# Connectors.net
KiCad netlist of a schematic drawn in Altium Designer
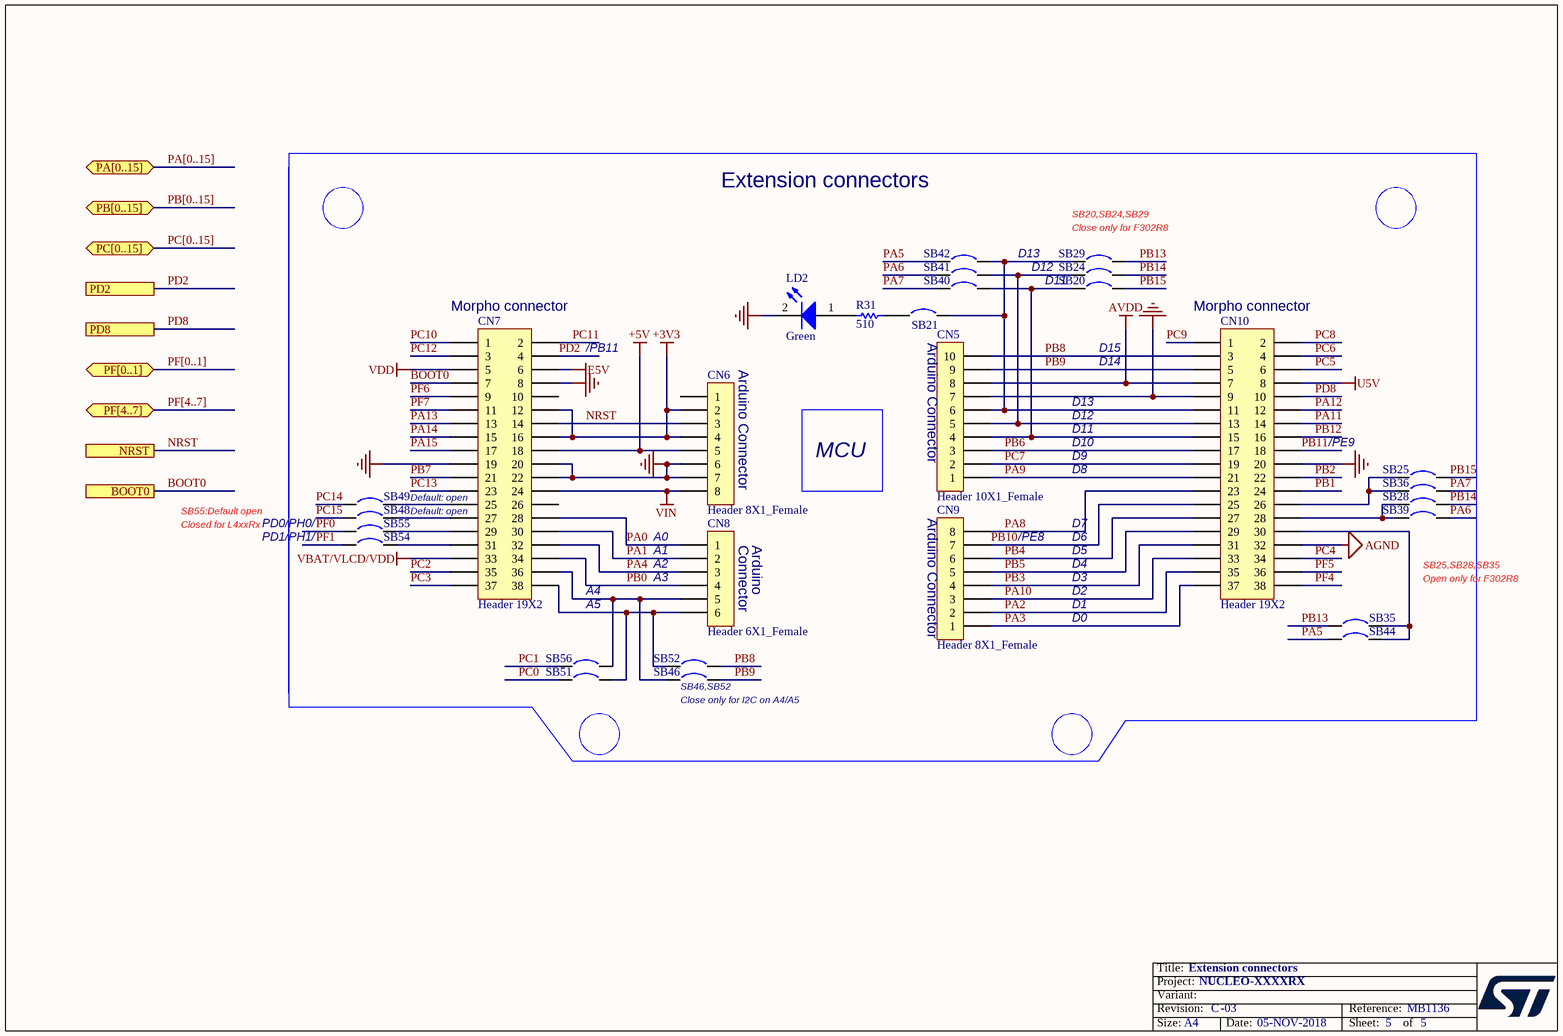
[diagram p0: Connectors.SchDoc]

(export (version "E")
  (design (tool "Eeschema 10.0.6"))
  (components
    (comp (ref "CN5")
      (value "Header 10X1_Female")
      (footprint "1*10P_FEMALE")
      (description "Header, 10-Pin, Single row,female")
      (fields (field (name "PUBLISHER") "Altium Limited"))
      (libsource (lib "Nucleo_64") (part "Header 10X1_Female"))
    )
    (comp (ref "CN6")
      (value "Header 8X1_Female")
      (footprint "1*8P_FEMALE")
      (description "Header, 8-Pin, Single row,female")
      (fields (field (name "PUBLISHER") "Altium Limited"))
      (libsource (lib "Nucleo_64") (part "Header 8X1_Female"))
    )
    (comp (ref "CN7")
      (value "Header 19X2")
      (footprint "2*19P")
      (description "Header, 19-Pin, Dual row")
      (fields (field (name "PUBLISHER") "Altium Limited"))
      (libsource (lib "Nucleo_64_1") (part "Header 19X2"))
    )
    (comp (ref "CN8")
      (value "Header 6X1_Female")
      (footprint "1*6P_FEMALE")
      (description "Header, 6-Pin, Single row,female")
      (fields (field (name "PUBLISHER") "Altium Limited"))
      (libsource (lib "Nucleo_64") (part "Header 6X1_Female"))
    )
    (comp (ref "CN9")
      (value "Header 8X1_Female")
      (footprint "1*8P_FEMALE")
      (description "Header, 8-Pin, Single row,female")
      (fields (field (name "PUBLISHER") "Altium Limited"))
      (libsource (lib "") (part "Header 8X1_Female_1"))
    )
    (comp (ref "CN10")
      (value "Header 19X2")
      (footprint "2*19P")
      (description "Header, 19-Pin, Dual row")
      (fields (field (name "PUBLISHER") "Altium Limited"))
      (libsource (lib "Nucleo_64_1") (part "Header 19X2"))
    )
    (comp (ref "LD2")
      (value "Green")
      (footprint "0603D")
      (description "Typical RED, GREEN, YELLOW, AMBER GaAs LED")
      (fields (field (name "PUBLISHER") "Altium Limited"))
      (libsource (lib "Miscellaneous Devices") (part "LED2"))
    )
    (comp (ref "R31")
      (value "510")
      (footprint "0603R")
      (description "Resistor")
      (fields (field (name "PUBLISHER") "Altium Limited"))
      (libsource (lib "Miscellaneous Devices") (part "Res1"))
    )
    (comp (ref "SB20")
      (value "Circuit Breaker")
      (footprint "JP2_SMD")
      (fields (field (name "PUBLISHER") "Altium Limited"))
      (libsource (lib "MCD_TOOLS") (part "Circuit Breaker"))
    )
    (comp (ref "SB21")
      (value "Circuit Breaker")
      (footprint "JP2_SMD")
      (fields (field (name "PUBLISHER") "Altium Limited"))
      (libsource (lib "MCD_TOOLS") (part "Circuit Breaker"))
    )
    (comp (ref "SB24")
      (value "Circuit Breaker")
      (footprint "JP2_SMD")
      (fields (field (name "PUBLISHER") "Altium Limited"))
      (libsource (lib "MCD_TOOLS") (part "Circuit Breaker"))
    )
    (comp (ref "SB25")
      (value "Circuit Breaker")
      (footprint "JP2_SMD")
      (fields (field (name "PUBLISHER") "Altium Limited"))
      (libsource (lib "") (part "Circuit Breaker_1"))
    )
    (comp (ref "SB28")
      (value "Circuit Breaker")
      (footprint "JP2_SMD")
      (fields (field (name "PUBLISHER") "Altium Limited"))
      (libsource (lib "") (part "Circuit Breaker_1"))
    )
    (comp (ref "SB29")
      (value "Circuit Breaker")
      (footprint "JP2_SMD")
      (fields (field (name "PUBLISHER") "Altium Limited"))
      (libsource (lib "MCD_TOOLS") (part "Circuit Breaker"))
    )
    (comp (ref "SB35")
      (value "Circuit Breaker")
      (footprint "JP2_SMD")
      (fields (field (name "PUBLISHER") "Altium Limited"))
      (libsource (lib "") (part "Circuit Breaker_1"))
    )
    (comp (ref "SB36")
      (value "Circuit Breaker")
      (footprint "JP2_SMD")
      (fields (field (name "PUBLISHER") "Altium Limited"))
      (libsource (lib "") (part "Circuit Breaker_1"))
    )
    (comp (ref "SB39")
      (value "Circuit Breaker")
      (footprint "JP2_SMD")
      (fields (field (name "PUBLISHER") "Altium Limited"))
      (libsource (lib "") (part "Circuit Breaker_1"))
    )
    (comp (ref "SB40")
      (value "Circuit Breaker")
      (footprint "JP2_SMD")
      (fields (field (name "PUBLISHER") "Altium Limited"))
      (libsource (lib "MCD_TOOLS") (part "Circuit Breaker"))
    )
    (comp (ref "SB41")
      (value "Circuit Breaker")
      (footprint "JP2_SMD")
      (fields (field (name "PUBLISHER") "Altium Limited"))
      (libsource (lib "MCD_TOOLS") (part "Circuit Breaker"))
    )
    (comp (ref "SB42")
      (value "Circuit Breaker")
      (footprint "JP2_SMD")
      (fields (field (name "PUBLISHER") "Altium Limited"))
      (libsource (lib "MCD_TOOLS") (part "Circuit Breaker"))
    )
    (comp (ref "SB44")
      (value "Circuit Breaker")
      (footprint "JP2_SMD")
      (fields (field (name "PUBLISHER") "Altium Limited"))
      (libsource (lib "") (part "Circuit Breaker_1"))
    )
    (comp (ref "SB46")
      (value "Circuit Breaker")
      (footprint "JP2_SMD")
      (fields (field (name "PUBLISHER") "Altium Limited"))
      (libsource (lib "MCD_TOOLS") (part "Circuit Breaker"))
    )
    (comp (ref "SB48")
      (value "Circuit Breaker")
      (footprint "JP2_SMD")
      (fields (field (name "PUBLISHER") "Altium Limited"))
      (libsource (lib "") (part "Circuit Breaker_1"))
    )
    (comp (ref "SB49")
      (value "Circuit Breaker")
      (footprint "JP2_SMD")
      (fields (field (name "PUBLISHER") "Altium Limited"))
      (libsource (lib "") (part "Circuit Breaker_1"))
    )
    (comp (ref "SB51")
      (value "Circuit Breaker")
      (footprint "JP2_SMD")
      (fields (field (name "PUBLISHER") "Altium Limited"))
      (libsource (lib "MCD_TOOLS") (part "Circuit Breaker"))
    )
    (comp (ref "SB52")
      (value "Circuit Breaker")
      (footprint "JP2_SMD")
      (fields (field (name "PUBLISHER") "Altium Limited"))
      (libsource (lib "MCD_TOOLS") (part "Circuit Breaker"))
    )
    (comp (ref "SB54")
      (value "Circuit Breaker")
      (footprint "JP2_SMD")
      (fields (field (name "PUBLISHER") "Altium Limited"))
      (libsource (lib "") (part "Circuit Breaker_1"))
    )
    (comp (ref "SB55")
      (value "Circuit Breaker")
      (footprint "JP2_SMD")
      (fields (field (name "PUBLISHER") "Altium Limited"))
      (libsource (lib "") (part "Circuit Breaker_1"))
    )
    (comp (ref "SB56")
      (value "Circuit Breaker")
      (footprint "JP2_SMD")
      (fields (field (name "PUBLISHER") "Altium Limited"))
      (libsource (lib "MCD_TOOLS") (part "Circuit Breaker"))
    )
  )
  (nets
    (net (code "1") (name "+3V3") (class "Default")
      (node (ref "CN6") (pin "2") (pinfunction "2_2") (pintype "passive"))
      (node (ref "CN6") (pin "4") (pinfunction "4_4") (pintype "passive"))
      (node (ref "CN7") (pin "12") (pinfunction "12_12") (pintype "passive"))
      (node (ref "CN7") (pin "16") (pinfunction "16_16") (pintype "passive"))
    )
    (net (code "2") (name "+5V") (class "Default")
      (node (ref "CN6") (pin "5") (pinfunction "5_5") (pintype "passive"))
      (node (ref "CN7") (pin "18") (pinfunction "18_18") (pintype "passive"))
    )
    (net (code "3") (name "/BOOT0") (class "Default")
      (node (ref "CN7") (pin "7") (pinfunction "7_7") (pintype "passive"))
    )
    (net (code "4") (name "/NRST") (class "Default")
      (node (ref "CN6") (pin "3") (pinfunction "3_3") (pintype "passive"))
      (node (ref "CN7") (pin "14") (pinfunction "14_14") (pintype "passive"))
    )
    (net (code "5") (name "/PA0") (class "Default")
      (node (ref "CN7") (pin "28") (pinfunction "28_28") (pintype "passive"))
      (node (ref "CN8") (pin "1") (pinfunction "1_1") (pintype "passive"))
    )
    (net (code "6") (name "/PA1") (class "Default")
      (node (ref "CN7") (pin "30") (pinfunction "30_30") (pintype "passive"))
      (node (ref "CN8") (pin "2") (pinfunction "2_2") (pintype "passive"))
    )
    (net (code "7") (name "/PA2") (class "Default")
      (node (ref "CN10") (pin "35") (pinfunction "35_35") (pintype "passive"))
      (node (ref "CN9") (pin "2") (pinfunction "2_2") (pintype "passive"))
    )
    (net (code "8") (name "/PA3") (class "Default")
      (node (ref "CN10") (pin "37") (pinfunction "37_37") (pintype "passive"))
      (node (ref "CN9") (pin "1") (pinfunction "1_1") (pintype "passive"))
    )
    (net (code "9") (name "/PA4") (class "Default")
      (node (ref "CN7") (pin "32") (pinfunction "32_32") (pintype "passive"))
      (node (ref "CN8") (pin "3") (pinfunction "3_3") (pintype "passive"))
    )
    (net (code "10") (name "/PA5") (class "Default")
      (node (ref "SB42") (pin "1") (pinfunction "1_1") (pintype "passive"))
      (node (ref "SB44") (pin "2") (pinfunction "2_2") (pintype "passive"))
    )
    (net (code "11") (name "/PA6") (class "Default")
      (node (ref "SB39") (pin "1") (pinfunction "1_1") (pintype "passive"))
      (node (ref "SB41") (pin "1") (pinfunction "1_1") (pintype "passive"))
    )
    (net (code "12") (name "/PA7") (class "Default")
      (node (ref "SB36") (pin "1") (pinfunction "1_1") (pintype "passive"))
      (node (ref "SB40") (pin "1") (pinfunction "1_1") (pintype "passive"))
    )
    (net (code "13") (name "/PA8") (class "Default")
      (node (ref "CN10") (pin "23") (pinfunction "23_23") (pintype "passive"))
      (node (ref "CN9") (pin "8") (pinfunction "8_8") (pintype "passive"))
    )
    (net (code "14") (name "/PA9") (class "Default")
      (node (ref "CN10") (pin "21") (pinfunction "21_21") (pintype "passive"))
      (node (ref "CN5") (pin "1") (pinfunction "1_1") (pintype "passive"))
    )
    (net (code "15") (name "/PA10") (class "Default")
      (node (ref "CN10") (pin "33") (pinfunction "33_33") (pintype "passive"))
      (node (ref "CN9") (pin "3") (pinfunction "3_3") (pintype "passive"))
    )
    (net (code "16") (name "/PA11") (class "Default")
      (node (ref "CN10") (pin "14") (pinfunction "14_14") (pintype "passive"))
    )
    (net (code "17") (name "/PA12") (class "Default")
      (node (ref "CN10") (pin "12") (pinfunction "12_12") (pintype "passive"))
    )
    (net (code "18") (name "/PA13") (class "Default")
      (node (ref "CN7") (pin "13") (pinfunction "13_13") (pintype "passive"))
    )
    (net (code "19") (name "/PA14") (class "Default")
      (node (ref "CN7") (pin "15") (pinfunction "15_15") (pintype "passive"))
    )
    (net (code "20") (name "/PA15") (class "Default")
      (node (ref "CN7") (pin "17") (pinfunction "17_17") (pintype "passive"))
    )
    (net (code "22") (name "/PB0") (class "Default")
      (node (ref "CN7") (pin "34") (pinfunction "34_34") (pintype "passive"))
      (node (ref "CN8") (pin "4") (pinfunction "4_4") (pintype "passive"))
    )
    (net (code "23") (name "/PB1") (class "Default")
      (node (ref "CN10") (pin "24") (pinfunction "24_24") (pintype "passive"))
    )
    (net (code "24") (name "/PB2") (class "Default")
      (node (ref "CN10") (pin "22") (pinfunction "22_22") (pintype "passive"))
    )
    (net (code "25") (name "/PB3") (class "Default")
      (node (ref "CN10") (pin "31") (pinfunction "31_31") (pintype "passive"))
      (node (ref "CN9") (pin "4") (pinfunction "4_4") (pintype "passive"))
    )
    (net (code "26") (name "/PB4") (class "Default")
      (node (ref "CN10") (pin "27") (pinfunction "27_27") (pintype "passive"))
      (node (ref "CN9") (pin "6") (pinfunction "6_6") (pintype "passive"))
    )
    (net (code "27") (name "/PB5") (class "Default")
      (node (ref "CN10") (pin "29") (pinfunction "29_29") (pintype "passive"))
      (node (ref "CN9") (pin "5") (pinfunction "5_5") (pintype "passive"))
    )
    (net (code "28") (name "/PB6") (class "Default")
      (node (ref "CN10") (pin "17") (pinfunction "17_17") (pintype "passive"))
      (node (ref "CN5") (pin "3") (pinfunction "3_3") (pintype "passive"))
    )
    (net (code "29") (name "/PB7") (class "Default")
      (node (ref "CN7") (pin "21") (pinfunction "21_21") (pintype "passive"))
    )
    (net (code "30") (name "/PB8") (class "Default")
      (node (ref "CN10") (pin "3") (pinfunction "3_3") (pintype "passive"))
      (node (ref "CN5") (pin "10") (pinfunction "10_10") (pintype "passive"))
      (node (ref "SB52") (pin "2") (pinfunction "2_2") (pintype "passive"))
    )
    (net (code "31") (name "/PB9") (class "Default")
      (node (ref "CN10") (pin "5") (pinfunction "5_5") (pintype "passive"))
      (node (ref "CN5") (pin "9") (pinfunction "9_9") (pintype "passive"))
      (node (ref "SB46") (pin "2") (pinfunction "2_2") (pintype "passive"))
    )
    (net (code "32") (name "/PB10") (class "Default")
      (node (ref "CN10") (pin "25") (pinfunction "25_25") (pintype "passive"))
      (node (ref "CN9") (pin "7") (pinfunction "7_7") (pintype "passive"))
    )
    (net (code "33") (name "/PB11") (class "Default")
      (node (ref "CN10") (pin "18") (pinfunction "18_18") (pintype "passive"))
    )
    (net (code "34") (name "/PB12") (class "Default")
      (node (ref "CN10") (pin "16") (pinfunction "16_16") (pintype "passive"))
    )
    (net (code "35") (name "/PB13") (class "Default")
      (node (ref "SB29") (pin "2") (pinfunction "2_2") (pintype "passive"))
      (node (ref "SB35") (pin "2") (pinfunction "2_2") (pintype "passive"))
    )
    (net (code "36") (name "/PB14") (class "Default")
      (node (ref "SB24") (pin "2") (pinfunction "2_2") (pintype "passive"))
      (node (ref "SB28") (pin "1") (pinfunction "1_1") (pintype "passive"))
    )
    (net (code "37") (name "/PB15") (class "Default")
      (node (ref "SB20") (pin "2") (pinfunction "2_2") (pintype "passive"))
      (node (ref "SB25") (pin "1") (pinfunction "1_1") (pintype "passive"))
    )
    (net (code "39") (name "/PC0") (class "Default")
      (node (ref "SB51") (pin "1") (pinfunction "1_1") (pintype "passive"))
    )
    (net (code "40") (name "/PC1") (class "Default")
      (node (ref "SB56") (pin "1") (pinfunction "1_1") (pintype "passive"))
    )
    (net (code "41") (name "/PC2") (class "Default")
      (node (ref "CN7") (pin "35") (pinfunction "35_35") (pintype "passive"))
    )
    (net (code "42") (name "/PC3") (class "Default")
      (node (ref "CN7") (pin "37") (pinfunction "37_37") (pintype "passive"))
    )
    (net (code "43") (name "/PC4") (class "Default")
      (node (ref "CN10") (pin "34") (pinfunction "34_34") (pintype "passive"))
    )
    (net (code "44") (name "/PC5") (class "Default")
      (node (ref "CN10") (pin "6") (pinfunction "6_6") (pintype "passive"))
    )
    (net (code "45") (name "/PC6") (class "Default")
      (node (ref "CN10") (pin "4") (pinfunction "4_4") (pintype "passive"))
    )
    (net (code "46") (name "/PC7") (class "Default")
      (node (ref "CN10") (pin "19") (pinfunction "19_19") (pintype "passive"))
      (node (ref "CN5") (pin "2") (pinfunction "2_2") (pintype "passive"))
    )
    (net (code "47") (name "/PC8") (class "Default")
      (node (ref "CN10") (pin "2") (pinfunction "2_2") (pintype "passive"))
    )
    (net (code "48") (name "/PC9") (class "Default")
      (node (ref "CN10") (pin "1") (pinfunction "1_1") (pintype "passive"))
    )
    (net (code "49") (name "/PC10") (class "Default")
      (node (ref "CN7") (pin "1") (pinfunction "1_1") (pintype "passive"))
    )
    (net (code "50") (name "/PC11") (class "Default")
      (node (ref "CN7") (pin "2") (pinfunction "2_2") (pintype "passive"))
    )
    (net (code "51") (name "/PC12") (class "Default")
      (node (ref "CN7") (pin "3") (pinfunction "3_3") (pintype "passive"))
    )
    (net (code "52") (name "/PC13") (class "Default")
      (node (ref "CN7") (pin "23") (pinfunction "23_23") (pintype "passive"))
    )
    (net (code "53") (name "/PC14") (class "Default")
      (node (ref "SB49") (pin "2") (pinfunction "2_2") (pintype "passive"))
    )
    (net (code "54") (name "/PC15") (class "Default")
      (node (ref "SB48") (pin "2") (pinfunction "2_2") (pintype "passive"))
    )
    (net (code "56") (name "/PD2") (class "Default")
      (node (ref "CN7") (pin "4") (pinfunction "4_4") (pintype "passive"))
    )
    (net (code "57") (name "/PD8") (class "Default")
      (node (ref "CN10") (pin "10") (pinfunction "10_10") (pintype "passive"))
    )
    (net (code "58") (name "/PF0") (class "Default")
      (node (ref "SB55") (pin "2") (pinfunction "2_2") (pintype "passive"))
    )
    (net (code "59") (name "/PF1") (class "Default")
      (node (ref "SB54") (pin "2") (pinfunction "2_2") (pintype "passive"))
    )
    (net (code "60") (name "/PF4") (class "Default")
      (node (ref "CN10") (pin "38") (pinfunction "38_38") (pintype "passive"))
    )
    (net (code "61") (name "/PF5") (class "Default")
      (node (ref "CN10") (pin "36") (pinfunction "36_36") (pintype "passive"))
    )
    (net (code "62") (name "/PF6") (class "Default")
      (node (ref "CN7") (pin "9") (pinfunction "9_9") (pintype "passive"))
    )
    (net (code "63") (name "/PF7") (class "Default")
      (node (ref "CN7") (pin "11") (pinfunction "11_11") (pintype "passive"))
    )
    (net (code "66") (name "AGND") (class "Default")
      (node (ref "CN10") (pin "32") (pinfunction "32_32") (pintype "passive"))
    )
    (net (code "67") (name "AVDD") (class "Default")
      (node (ref "CN10") (pin "7") (pinfunction "7_7") (pintype "passive"))
      (node (ref "CN5") (pin "8") (pinfunction "8_8") (pintype "passive"))
    )
    (net (code "68") (name "E5V") (class "Default")
      (node (ref "CN7") (pin "6") (pinfunction "6_6") (pintype "passive"))
    )
    (net (code "69") (name "GND") (class "Default")
      (node (ref "CN10") (pin "20") (pinfunction "20_20") (pintype "passive"))
      (node (ref "CN10") (pin "9") (pinfunction "9_9") (pintype "passive"))
      (node (ref "CN5") (pin "7") (pinfunction "7_7") (pintype "passive"))
      (node (ref "CN6") (pin "6") (pinfunction "6_6") (pintype "passive"))
      (node (ref "CN6") (pin "7") (pinfunction "7_7") (pintype "passive"))
      (node (ref "CN7") (pin "19") (pinfunction "19_19") (pintype "passive"))
      (node (ref "CN7") (pin "20") (pinfunction "20_20") (pintype "passive"))
      (node (ref "CN7") (pin "22") (pinfunction "22_22") (pintype "passive"))
      (node (ref "CN7") (pin "8") (pinfunction "8_8") (pintype "passive"))
      (node (ref "LD2") (pin "2") (pinfunction "K_2") (pintype "passive"))
    )
    (net (code "70") (name "Net-(CN7-Pad25)") (class "Default")
      (node (ref "CN7") (pin "25") (pinfunction "25_25") (pintype "passive"))
      (node (ref "SB49") (pin "1") (pinfunction "1_1") (pintype "passive"))
    )
    (net (code "71") (name "Net-(CN7-Pad27)") (class "Default")
      (node (ref "CN7") (pin "27") (pinfunction "27_27") (pintype "passive"))
      (node (ref "SB48") (pin "1") (pinfunction "1_1") (pintype "passive"))
    )
    (net (code "72") (name "Net-(CN7-Pad29)") (class "Default")
      (node (ref "CN7") (pin "29") (pinfunction "29_29") (pintype "passive"))
      (node (ref "SB55") (pin "1") (pinfunction "1_1") (pintype "passive"))
    )
    (net (code "73") (name "Net-(CN7-Pad31)") (class "Default")
      (node (ref "CN7") (pin "31") (pinfunction "31_31") (pintype "passive"))
      (node (ref "SB54") (pin "1") (pinfunction "1_1") (pintype "passive"))
    )
    (net (code "74") (name "Net-(CN7-Pad36)") (class "Default")
      (node (ref "CN7") (pin "36") (pinfunction "36_36") (pintype "passive"))
      (node (ref "CN8") (pin "5") (pinfunction "5_5") (pintype "passive"))
      (node (ref "SB46") (pin "1") (pinfunction "1_1") (pintype "passive"))
      (node (ref "SB56") (pin "2") (pinfunction "2_2") (pintype "passive"))
    )
    (net (code "75") (name "Net-(CN7-Pad38)") (class "Default")
      (node (ref "CN7") (pin "38") (pinfunction "38_38") (pintype "passive"))
      (node (ref "CN8") (pin "6") (pinfunction "6_6") (pintype "passive"))
      (node (ref "SB51") (pin "2") (pinfunction "2_2") (pintype "passive"))
      (node (ref "SB52") (pin "1") (pinfunction "1_1") (pintype "passive"))
    )
    (net (code "76") (name "Net-(CN10-Pad11)") (class "Default")
      (node (ref "CN10") (pin "11") (pinfunction "11_11") (pintype "passive"))
      (node (ref "CN5") (pin "6") (pinfunction "6_6") (pintype "passive"))
      (node (ref "SB21") (pin "2") (pinfunction "2_2") (pintype "passive"))
      (node (ref "SB29") (pin "1") (pinfunction "1_1") (pintype "passive"))
      (node (ref "SB42") (pin "2") (pinfunction "2_2") (pintype "passive"))
    )
    (net (code "77") (name "Net-(CN10-Pad13)") (class "Default")
      (node (ref "CN10") (pin "13") (pinfunction "13_13") (pintype "passive"))
      (node (ref "CN5") (pin "5") (pinfunction "5_5") (pintype "passive"))
      (node (ref "SB24") (pin "1") (pinfunction "1_1") (pintype "passive"))
      (node (ref "SB41") (pin "2") (pinfunction "2_2") (pintype "passive"))
    )
    (net (code "78") (name "Net-(CN10-Pad15)") (class "Default")
      (node (ref "CN10") (pin "15") (pinfunction "15_15") (pintype "passive"))
      (node (ref "CN5") (pin "4") (pinfunction "4_4") (pintype "passive"))
      (node (ref "SB20") (pin "1") (pinfunction "1_1") (pintype "passive"))
      (node (ref "SB40") (pin "2") (pinfunction "2_2") (pintype "passive"))
    )
    (net (code "79") (name "Net-(CN10-Pad26)") (class "Default")
      (node (ref "CN10") (pin "26") (pinfunction "26_26") (pintype "passive"))
      (node (ref "SB25") (pin "2") (pinfunction "2_2") (pintype "passive"))
      (node (ref "SB36") (pin "2") (pinfunction "2_2") (pintype "passive"))
    )
    (net (code "80") (name "Net-(CN10-Pad28)") (class "Default")
      (node (ref "CN10") (pin "28") (pinfunction "28_28") (pintype "passive"))
      (node (ref "SB28") (pin "2") (pinfunction "2_2") (pintype "passive"))
      (node (ref "SB39") (pin "2") (pinfunction "2_2") (pintype "passive"))
    )
    (net (code "81") (name "Net-(CN10-Pad30)") (class "Default")
      (node (ref "CN10") (pin "30") (pinfunction "30_30") (pintype "passive"))
      (node (ref "SB35") (pin "1") (pinfunction "1_1") (pintype "passive"))
      (node (ref "SB44") (pin "1") (pinfunction "1_1") (pintype "passive"))
    )
    (net (code "82") (name "Net-(LD2-A)") (class "Default")
      (node (ref "LD2") (pin "1") (pinfunction "A_1") (pintype "passive"))
      (node (ref "R31") (pin "2") (pinfunction "2_2") (pintype "passive"))
    )
    (net (code "83") (name "Net-(R31-Pad1)") (class "Default")
      (node (ref "R31") (pin "1") (pinfunction "1_1") (pintype "passive"))
      (node (ref "SB21") (pin "1") (pinfunction "1_1") (pintype "passive"))
    )
    (net (code "84") (name "U5V") (class "Default")
      (node (ref "CN10") (pin "8") (pinfunction "8_8") (pintype "passive"))
    )
    (net (code "85") (name "VBAT{slash}VLCD{slash}VDD") (class "Default")
      (node (ref "CN7") (pin "33") (pinfunction "33_33") (pintype "passive"))
    )
    (net (code "86") (name "VDD") (class "Default")
      (node (ref "CN7") (pin "5") (pinfunction "5_5") (pintype "passive"))
    )
    (net (code "87") (name "VIN") (class "Default")
      (node (ref "CN6") (pin "8") (pinfunction "8_8") (pintype "passive"))
      (node (ref "CN7") (pin "24") (pinfunction "24_24") (pintype "passive"))
    )
    (net (code "88") (name "unconnected-(CN6-Pad1)") (class "Default")
      (node (ref "CN6") (pin "1") (pinfunction "1_1") (pintype "passive"))
    )
    (net (code "89") (name "unconnected-(CN7-Pad10)") (class "Default")
      (node (ref "CN7") (pin "10") (pinfunction "10_10") (pintype "passive"))
    )
    (net (code "90") (name "unconnected-(CN7-Pad26)") (class "Default")
      (node (ref "CN7") (pin "26") (pinfunction "26_26") (pintype "passive"))
    )
  )
)
